# BpodFSM_r2_4.net
KiCad netlist of a schematic drawn in EAGLE
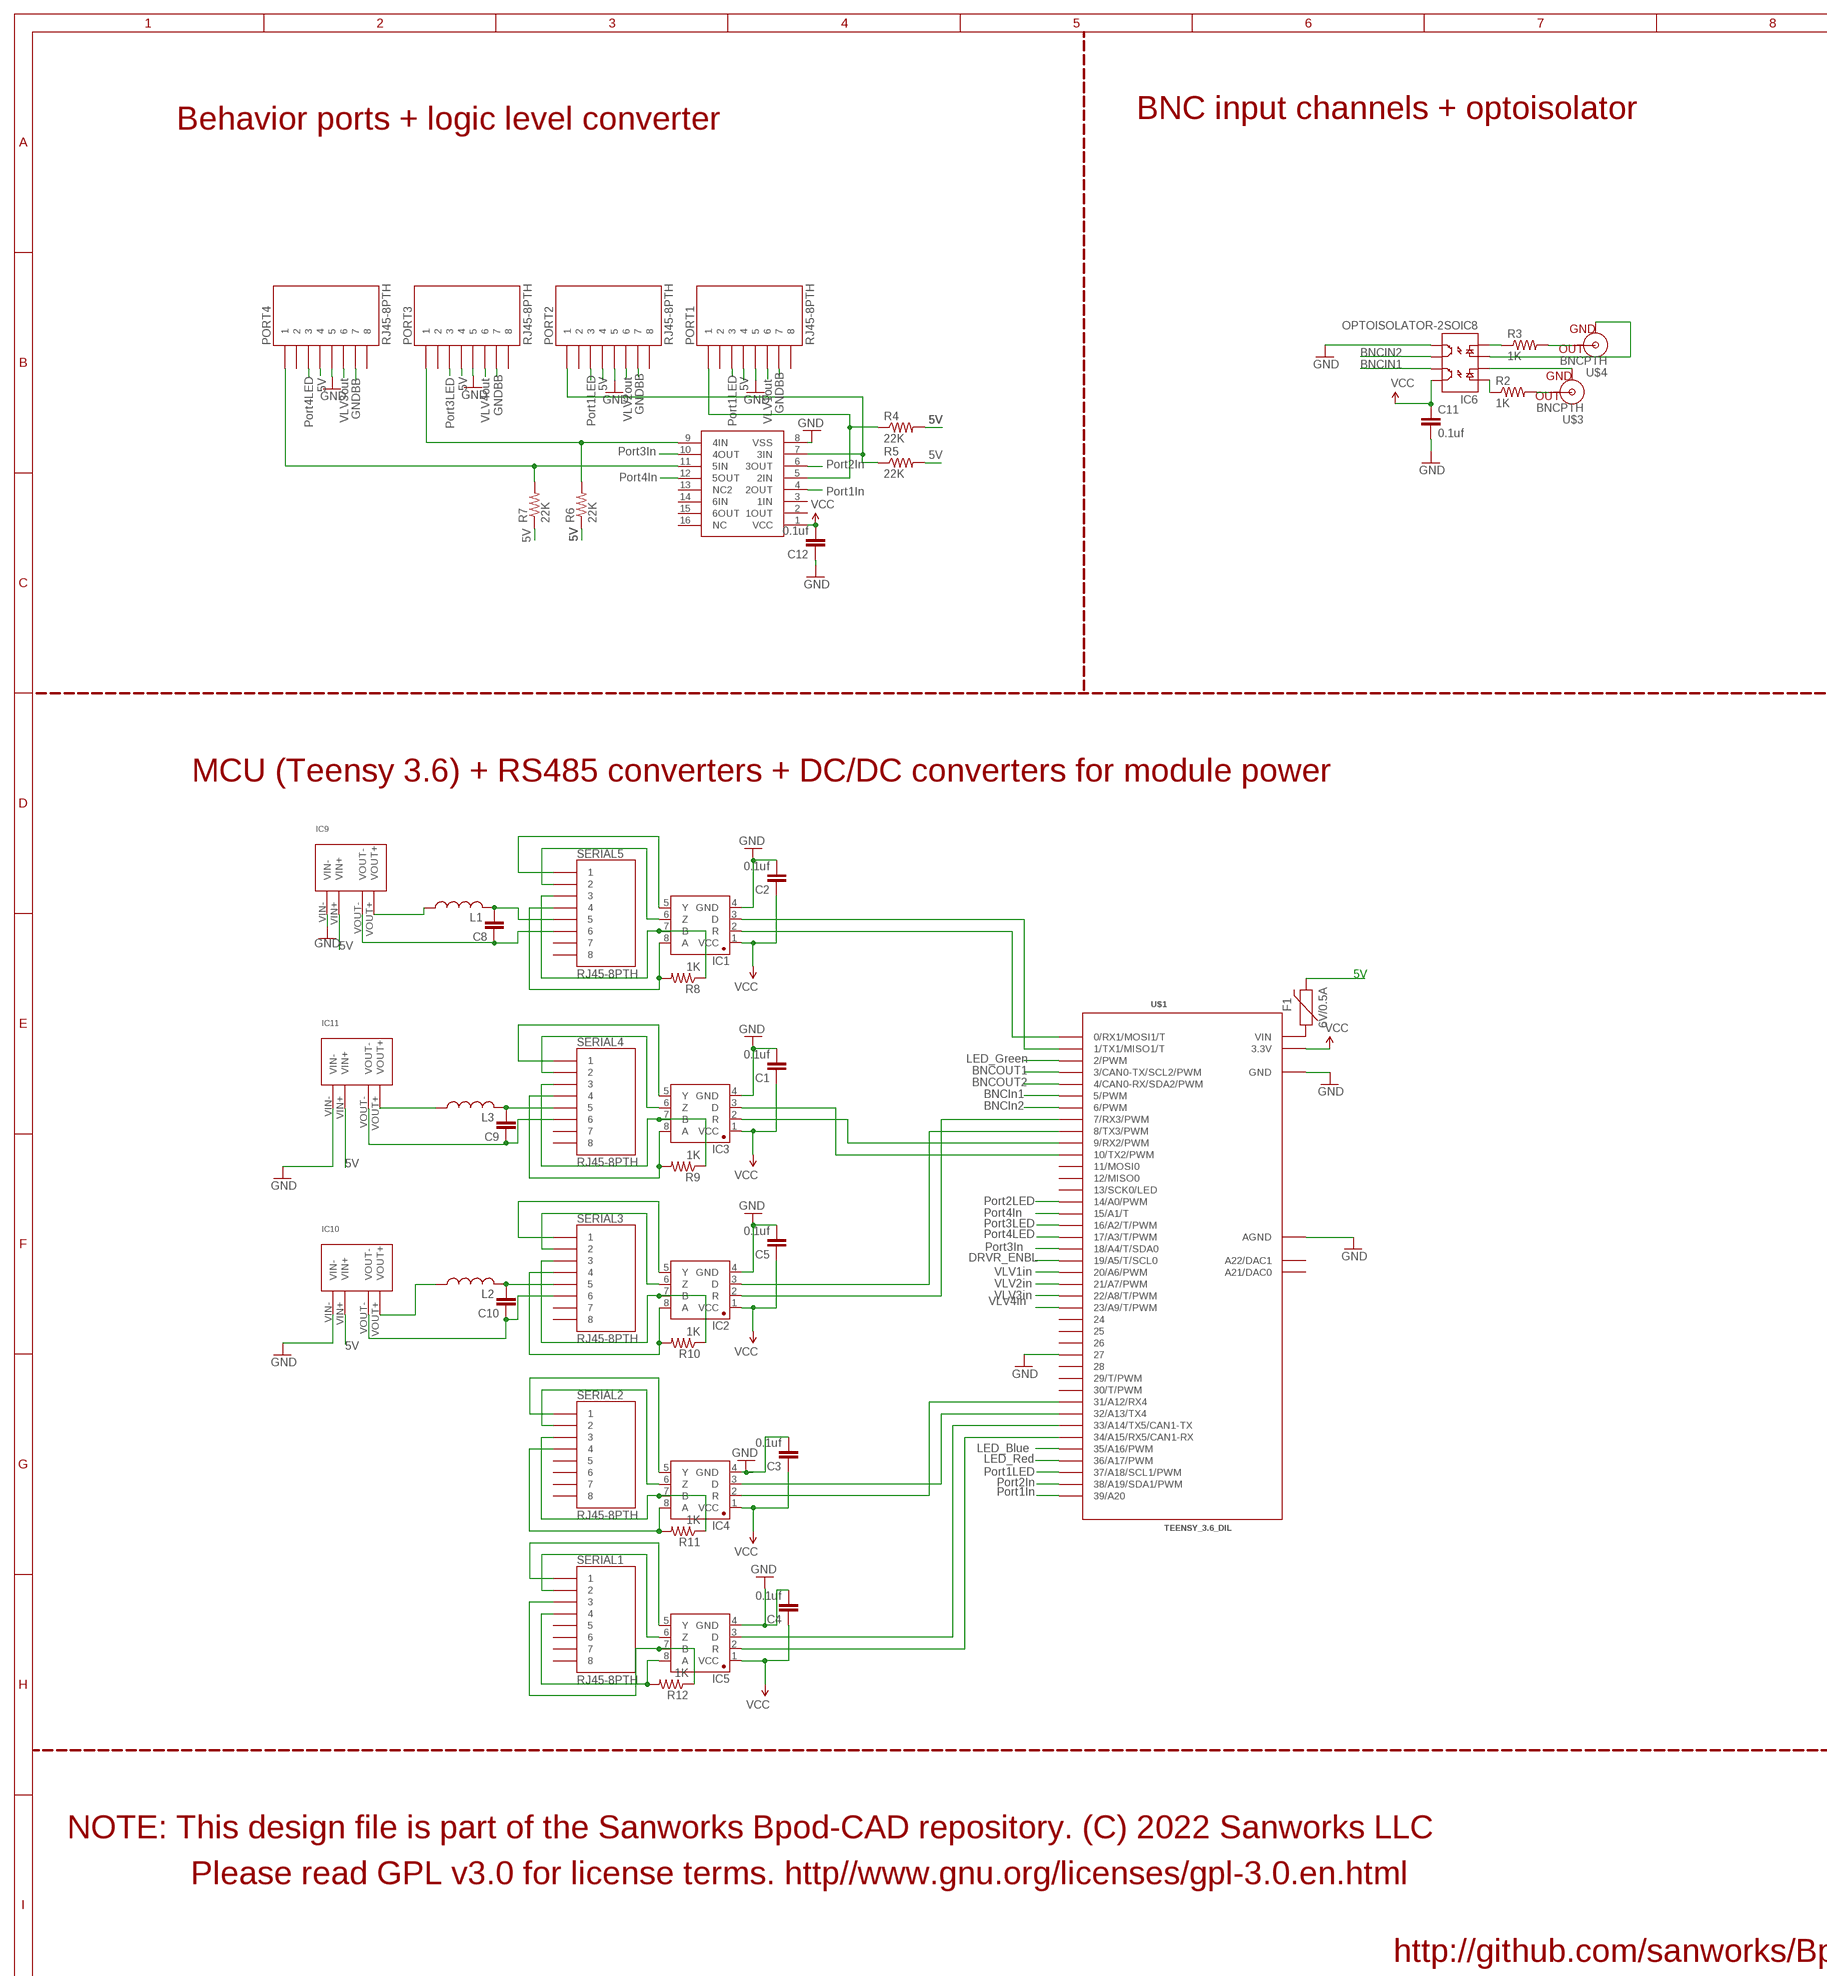
[diagram p0: schematic, sheet 1, part 1 of 2]
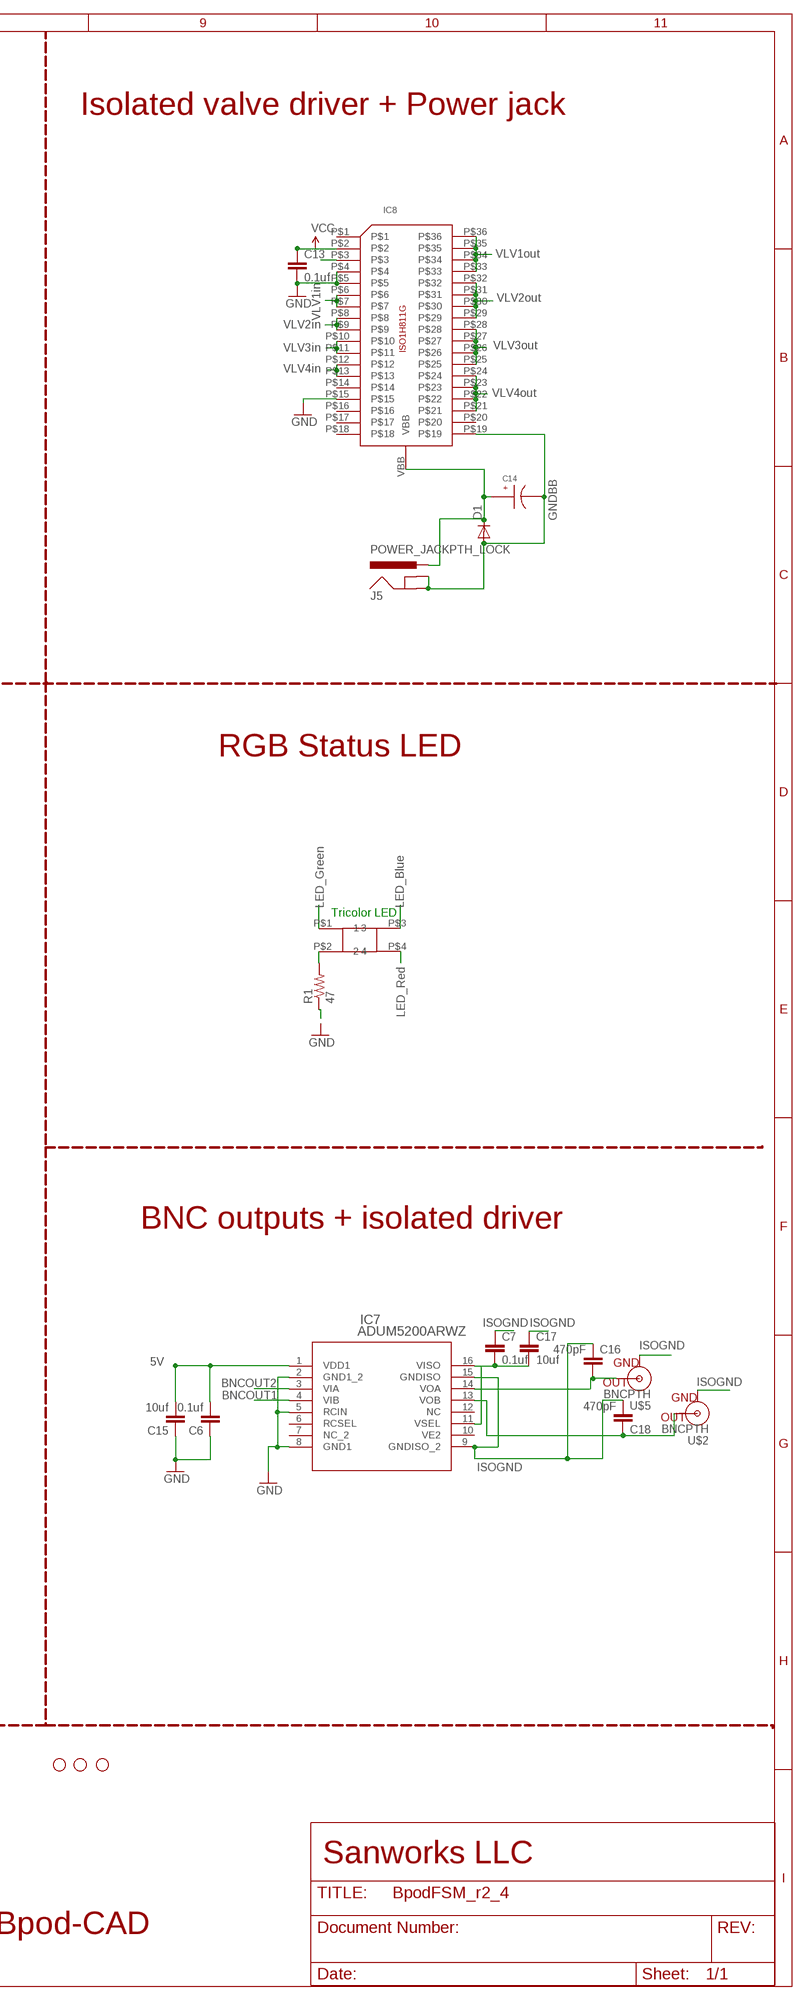
[diagram p1: schematic, sheet 1, part 2 of 2]

(export (version "E")
  (design (tool "Eeschema 10.0.6"))
  (components
    (comp (ref "C1")
      (value "0.1uf")
      (footprint "eagle-import:1206@1")
      (libsource (lib "eagle-import") (part "CAP1206"))
    )
    (comp (ref "C2")
      (value "0.1uf")
      (footprint "eagle-import:1206@1")
      (libsource (lib "eagle-import") (part "CAP1206"))
    )
    (comp (ref "C3")
      (value "0.1uf")
      (footprint "eagle-import:1206@1")
      (libsource (lib "eagle-import") (part "CAP1206"))
    )
    (comp (ref "C4")
      (value "0.1uf")
      (footprint "eagle-import:1206@1")
      (libsource (lib "eagle-import") (part "CAP1206"))
    )
    (comp (ref "C5")
      (value "0.1uf")
      (footprint "eagle-import:1206@1")
      (libsource (lib "eagle-import") (part "CAP1206"))
    )
    (comp (ref "C6")
      (value "0.1uf")
      (footprint "eagle-import:0805")
      (libsource (lib "eagle-import") (part "1.0UF-0805-25V-10%"))
    )
    (comp (ref "C7")
      (value "0.1uf")
      (footprint "eagle-import:0805")
      (libsource (lib "eagle-import") (part "1.0UF-0805-25V-10%"))
    )
    (comp (ref "C8")
      (value "CAP1206")
      (footprint "eagle-import:1206@1")
      (libsource (lib "eagle-import") (part "CAP1206"))
    )
    (comp (ref "C9")
      (value "CAP1206")
      (footprint "eagle-import:1206@1")
      (libsource (lib "eagle-import") (part "CAP1206"))
    )
    (comp (ref "C10")
      (value "CAP1206")
      (footprint "eagle-import:1206@1")
      (libsource (lib "eagle-import") (part "CAP1206"))
    )
    (comp (ref "C11")
      (value "0.1uf")
      (footprint "eagle-import:1206@1")
      (libsource (lib "eagle-import") (part "CAP1206"))
    )
    (comp (ref "C12")
      (value "0.1uf")
      (footprint "eagle-import:1206@1")
      (libsource (lib "eagle-import") (part "CAP1206"))
    )
    (comp (ref "C13")
      (value "0.1uf")
      (footprint "eagle-import:1206@1")
      (libsource (lib "eagle-import") (part "CAP1206"))
    )
    (comp (ref "C14")
      (value "EEE-FK1H100UR")
      (footprint "eagle-import:EEE-FK1H100UR")
      (libsource (lib "eagle-import") (part "EEE-FK1H100UR"))
    )
    (comp (ref "C15")
      (value "10uf")
      (footprint "eagle-import:1206@1")
      (libsource (lib "eagle-import") (part "CAP1206"))
    )
    (comp (ref "C16")
      (value "470pF")
      (footprint "eagle-import:0805")
      (libsource (lib "eagle-import") (part "1.0UF-0805-25V-10%"))
    )
    (comp (ref "C17")
      (value "10uf")
      (footprint "eagle-import:1206@1")
      (libsource (lib "eagle-import") (part "CAP1206"))
    )
    (comp (ref "C18")
      (value "470pF")
      (footprint "eagle-import:0805")
      (libsource (lib "eagle-import") (part "1.0UF-0805-25V-10%"))
    )
    (comp (ref "D1")
      (value "DIODE-DO214AA")
      (footprint "eagle-import:DO214AA")
      (libsource (lib "eagle-import") (part "DIODE-DO214AA"))
    )
    (comp (ref "F1")
      (value "6V/0.5A")
      (footprint "eagle-import:1206")
      (libsource (lib "eagle-import") (part "PPTC_HALF-AMP"))
    )
    (comp (ref "IC1")
      (value "SN65HVD31DR")
      (footprint "eagle-import:SO08")
      (libsource (lib "eagle-import") (part "SN65HVD31DR"))
    )
    (comp (ref "IC2")
      (value "SN65HVD31DR")
      (footprint "eagle-import:SO08")
      (libsource (lib "eagle-import") (part "SN65HVD31DR"))
    )
    (comp (ref "IC3")
      (value "SN65HVD31DR")
      (footprint "eagle-import:SO08")
      (libsource (lib "eagle-import") (part "SN65HVD31DR"))
    )
    (comp (ref "IC4")
      (value "SN65HVD31DR")
      (footprint "eagle-import:SO08")
      (libsource (lib "eagle-import") (part "SN65HVD31DR"))
    )
    (comp (ref "IC5")
      (value "SN65HVD31DR")
      (footprint "eagle-import:SO08")
      (libsource (lib "eagle-import") (part "SN65HVD31DR"))
    )
    (comp (ref "IC6")
      (value "OPTOISOLATOR-2SOIC8")
      (footprint "eagle-import:SO08-2")
      (libsource (lib "eagle-import") (part "OPTOISOLATOR-2SOIC8"))
    )
    (comp (ref "IC7")
      (value "ADUM5200ARWZ")
      (footprint "eagle-import:RW_16")
      (libsource (lib "eagle-import") (part "ADUM5200ARWZ"))
    )
    (comp (ref "IC8")
      (value "ISO1H811G")
      (footprint "eagle-import:ISO1H811G")
      (libsource (lib "eagle-import") (part "ISO1H811G"))
    )
    (comp (ref "IC9")
      (value "NME0509SC")
      (footprint "eagle-import:NME0509SC")
      (libsource (lib "eagle-import") (part "NME0509SC"))
    )
    (comp (ref "IC10")
      (value "NME0509SC")
      (footprint "eagle-import:NME0509SC")
      (libsource (lib "eagle-import") (part "NME0509SC"))
    )
    (comp (ref "IC11")
      (value "NME0509SC")
      (footprint "eagle-import:NME0509SC")
      (libsource (lib "eagle-import") (part "NME0509SC"))
    )
    (comp (ref "IC12")
      (value "CD4050")
      (footprint "eagle-import:SO16")
      (libsource (lib "eagle-import") (part "CD4050"))
    )
    (comp (ref "J5")
      (value "POWER_JACKPTH_LOCK")
      (footprint "eagle-import:POWER_JACK_PTH_LOCK")
      (libsource (lib "eagle-import") (part "POWER_JACKPTH_LOCK"))
    )
    (comp (ref "JP3")
      (value "STAND-OFF")
      (footprint "eagle-import:STAND-OFF")
      (libsource (lib "eagle-import") (part "STAND-OFF"))
    )
    (comp (ref "JP4")
      (value "STAND-OFF")
      (footprint "eagle-import:STAND-OFF")
      (libsource (lib "eagle-import") (part "STAND-OFF"))
    )
    (comp (ref "JP5")
      (value "STAND-OFF")
      (footprint "eagle-import:STAND-OFF")
      (libsource (lib "eagle-import") (part "STAND-OFF"))
    )
    (comp (ref "L1")
      (value "L-USL3225M")
      (footprint "eagle-import:L3225M")
      (libsource (lib "eagle-import") (part "L-USL3225M"))
    )
    (comp (ref "L2")
      (value "L-USL3225M")
      (footprint "eagle-import:L3225M")
      (libsource (lib "eagle-import") (part "L-USL3225M"))
    )
    (comp (ref "L3")
      (value "L-USL3225M")
      (footprint "eagle-import:L3225M")
      (libsource (lib "eagle-import") (part "L-USL3225M"))
    )
    (comp (ref "PORT1")
      (value "RJ45-8PTH")
      (footprint "eagle-import:RJ45-8")
      (libsource (lib "eagle-import") (part "RJ45-8PTH"))
    )
    (comp (ref "PORT2")
      (value "RJ45-8PTH")
      (footprint "eagle-import:RJ45-8")
      (libsource (lib "eagle-import") (part "RJ45-8PTH"))
    )
    (comp (ref "PORT3")
      (value "RJ45-8PTH")
      (footprint "eagle-import:RJ45-8")
      (libsource (lib "eagle-import") (part "RJ45-8PTH"))
    )
    (comp (ref "PORT4")
      (value "RJ45-8PTH")
      (footprint "eagle-import:RJ45-8")
      (libsource (lib "eagle-import") (part "RJ45-8PTH"))
    )
    (comp (ref "R1")
      (value "47")
      (footprint "eagle-import:1206")
      (libsource (lib "eagle-import") (part "RESISTOR1206"))
    )
    (comp (ref "R2")
      (value "1K")
      (footprint "eagle-import:1206")
      (libsource (lib "eagle-import") (part "SparkFun-Resistors_RESISTOR1206"))
    )
    (comp (ref "R3")
      (value "1K")
      (footprint "eagle-import:1206")
      (libsource (lib "eagle-import") (part "SparkFun-Resistors_RESISTOR1206"))
    )
    (comp (ref "R4")
      (value "22K")
      (footprint "eagle-import:1206")
      (libsource (lib "eagle-import") (part "SparkFun-Resistors_RESISTOR1206"))
    )
    (comp (ref "R5")
      (value "22K")
      (footprint "eagle-import:1206")
      (libsource (lib "eagle-import") (part "SparkFun-Resistors_RESISTOR1206"))
    )
    (comp (ref "R6")
      (value "22K")
      (footprint "eagle-import:1206")
      (libsource (lib "eagle-import") (part "SparkFun-Resistors_RESISTOR1206"))
    )
    (comp (ref "R7")
      (value "22K")
      (footprint "eagle-import:1206")
      (libsource (lib "eagle-import") (part "SparkFun-Resistors_RESISTOR1206"))
    )
    (comp (ref "R8")
      (value "1K")
      (footprint "eagle-import:1206")
      (libsource (lib "eagle-import") (part "SparkFun-Resistors_RESISTOR1206"))
    )
    (comp (ref "R9")
      (value "1K")
      (footprint "eagle-import:1206")
      (libsource (lib "eagle-import") (part "SparkFun-Resistors_RESISTOR1206"))
    )
    (comp (ref "R10")
      (value "1K")
      (footprint "eagle-import:1206")
      (libsource (lib "eagle-import") (part "SparkFun-Resistors_RESISTOR1206"))
    )
    (comp (ref "R11")
      (value "1K")
      (footprint "eagle-import:1206")
      (libsource (lib "eagle-import") (part "SparkFun-Resistors_RESISTOR1206"))
    )
    (comp (ref "R12")
      (value "1K")
      (footprint "eagle-import:1206")
      (libsource (lib "eagle-import") (part "SparkFun-Resistors_RESISTOR1206"))
    )
    (comp (ref "SERIAL1")
      (value "RJ45-8PTH")
      (footprint "eagle-import:RJ45-8")
      (libsource (lib "eagle-import") (part "RJ45-8PTH"))
    )
    (comp (ref "SERIAL2")
      (value "RJ45-8PTH")
      (footprint "eagle-import:RJ45-8")
      (libsource (lib "eagle-import") (part "RJ45-8PTH"))
    )
    (comp (ref "SERIAL3")
      (value "RJ45-8PTH")
      (footprint "eagle-import:RJ45-8")
      (libsource (lib "eagle-import") (part "RJ45-8PTH"))
    )
    (comp (ref "SERIAL4")
      (value "RJ45-8PTH")
      (footprint "eagle-import:RJ45-8")
      (libsource (lib "eagle-import") (part "RJ45-8PTH"))
    )
    (comp (ref "SERIAL5")
      (value "RJ45-8PTH")
      (footprint "eagle-import:RJ45-8")
      (libsource (lib "eagle-import") (part "RJ45-8PTH"))
    )
    (comp (ref "U$1")
      (value "TEENSY_3.6_DIL")
      (footprint "eagle-import:TEENSY_3.6_DIL")
      (libsource (lib "eagle-import") (part "TEENSY_3.6_DIL"))
    )
    (comp (ref "U$2")
      (value "BNCPTH")
      (footprint "eagle-import:BNC")
      (libsource (lib "eagle-import") (part "BNCPTH"))
    )
    (comp (ref "U$3")
      (value "BNCPTH")
      (footprint "eagle-import:BNC")
      (libsource (lib "eagle-import") (part "BNCPTH"))
    )
    (comp (ref "U$4")
      (value "BNCPTH")
      (footprint "eagle-import:BNC")
      (libsource (lib "eagle-import") (part "BNCPTH"))
    )
    (comp (ref "U$5")
      (value "BNCPTH")
      (footprint "eagle-import:BNC")
      (libsource (lib "eagle-import") (part "BNCPTH"))
    )
    (comp (ref "U$8")
      (value "SQUARE_TRICOLOR_LED")
      (footprint "eagle-import:SQUARE_TRICOLOR_LED")
      (libsource (lib "eagle-import") (part "SQUARE_TRICOLOR_LED"))
    )
  )
  (nets
    (net (code "1") (name "/5V") (class "Default")
      (node (ref "C15") (pin "2") (pinfunction "2_2") (pintype "passive"))
      (node (ref "C6") (pin "2") (pinfunction "2_2") (pintype "passive"))
      (node (ref "F1") (pin "2") (pinfunction "2_2") (pintype "bidirectional"))
      (node (ref "IC10") (pin "VIN+") (pinfunction "VIN+_VIN+") (pintype "bidirectional"))
      (node (ref "IC11") (pin "VIN+") (pinfunction "VIN+_VIN+") (pintype "bidirectional"))
      (node (ref "IC7") (pin "1") (pinfunction "VDD1_1") (pintype "passive"))
      (node (ref "IC9") (pin "VIN+") (pinfunction "VIN+_VIN+") (pintype "bidirectional"))
      (node (ref "PORT1") (pin "4") (pinfunction "4_4") (pintype "bidirectional"))
      (node (ref "PORT2") (pin "4") (pinfunction "4_4") (pintype "bidirectional"))
      (node (ref "PORT3") (pin "4") (pinfunction "4_4") (pintype "bidirectional"))
      (node (ref "PORT4") (pin "4") (pinfunction "4_4") (pintype "bidirectional"))
      (node (ref "R4") (pin "2") (pinfunction "2_2") (pintype "passive"))
      (node (ref "R5") (pin "2") (pinfunction "2_2") (pintype "passive"))
      (node (ref "R6") (pin "1") (pinfunction "1_1") (pintype "passive"))
      (node (ref "R7") (pin "1") (pinfunction "1_1") (pintype "passive"))
    )
    (net (code "2") (name "/BNCIN1") (class "Default")
      (node (ref "IC6") (pin "7") (pinfunction "EM1_7") (pintype "bidirectional"))
      (node (ref "U$1") (pin "6") (pinfunction "6/PWM_6") (pintype "bidirectional"))
    )
    (net (code "3") (name "/BNCIN2") (class "Default")
      (node (ref "IC6") (pin "6") (pinfunction "CL2_6") (pintype "bidirectional"))
      (node (ref "U$1") (pin "5") (pinfunction "5/PWM_5") (pintype "bidirectional"))
    )
    (net (code "4") (name "/BNCOUT1") (class "Default")
      (node (ref "IC7") (pin "4") (pinfunction "VIB_4") (pintype "passive"))
      (node (ref "U$1") (pin "4") (pinfunction "4/CAN0-RX/SDA2/PWM_4") (pintype "bidirectional"))
    )
    (net (code "5") (name "/BNCOUT2") (class "Default")
      (node (ref "IC7") (pin "3") (pinfunction "VIA_3") (pintype "passive"))
      (node (ref "U$1") (pin "3") (pinfunction "3/CAN0-TX/SCL2/PWM_3") (pintype "bidirectional"))
    )
    (net (code "6") (name "/DRVR_ENBL") (class "Default")
      (node (ref "IC8") (pin "P$3") (pinfunction "P$3_P$3") (pintype "bidirectional"))
      (node (ref "U$1") (pin "19/A5") (pinfunction "19/A5/T/SCL0_19/A5") (pintype "bidirectional"))
    )
    (net (code "7") (name "/GNDBB") (class "Default")
      (node (ref "C14") (pin "CATHODE") (pinfunction "CATHODE_CATHODE") (pintype "bidirectional"))
      (node (ref "D1") (pin "A") (pinfunction "A_A") (pintype "passive"))
      (node (ref "IC8") (pin "P$19") (pinfunction "P$19_P$19") (pintype "bidirectional"))
      (node (ref "J5") (pin "GND") (pinfunction "GND_GND") (pintype "bidirectional"))
      (node (ref "J5") (pin "GNDBREAK") (pinfunction "GNDBREAK_GNDBREAK") (pintype "bidirectional"))
      (node (ref "PORT1") (pin "7") (pinfunction "7_7") (pintype "bidirectional"))
      (node (ref "PORT2") (pin "7") (pinfunction "7_7") (pintype "bidirectional"))
      (node (ref "PORT3") (pin "7") (pinfunction "7_7") (pintype "bidirectional"))
      (node (ref "PORT4") (pin "7") (pinfunction "7_7") (pintype "bidirectional"))
    )
    (net (code "8") (name "/ISOGND") (class "Default")
      (node (ref "C16") (pin "2") (pinfunction "2_2") (pintype "passive"))
      (node (ref "C17") (pin "1") (pinfunction "1_1") (pintype "passive"))
      (node (ref "C18") (pin "2") (pinfunction "2_2") (pintype "passive"))
      (node (ref "C7") (pin "1") (pinfunction "1_1") (pintype "passive"))
      (node (ref "IC7") (pin "15") (pinfunction "GNDISO_15") (pintype "passive"))
      (node (ref "IC7") (pin "9") (pinfunction "GNDISO_2_9") (pintype "passive"))
      (node (ref "U$2") (pin "GND") (pinfunction "GND_GND") (pintype "bidirectional"))
      (node (ref "U$5") (pin "GND") (pinfunction "GND_GND") (pintype "bidirectional"))
    )
    (net (code "9") (name "/LED_BLUE") (class "Default")
      (node (ref "U$1") (pin "35/A16") (pinfunction "35/A16/PWM_35/A16") (pintype "bidirectional"))
      (node (ref "U$8") (pin "P$3") (pinfunction "3_P$3") (pintype "bidirectional"))
    )
    (net (code "10") (name "/LED_GREEN") (class "Default")
      (node (ref "U$1") (pin "2") (pinfunction "2/PWM_2") (pintype "bidirectional"))
      (node (ref "U$8") (pin "P$1") (pinfunction "1_P$1") (pintype "bidirectional"))
    )
    (net (code "11") (name "/LED_RED") (class "Default")
      (node (ref "U$1") (pin "36/A17") (pinfunction "36/A17/PWM_36/A17") (pintype "bidirectional"))
      (node (ref "U$8") (pin "P$4") (pinfunction "4_P$4") (pintype "bidirectional"))
    )
    (net (code "12") (name "/PORT1IN") (class "Default")
      (node (ref "IC12") (pin "4") (pinfunction "2OUT_4") (pintype "bidirectional"))
      (node (ref "U$1") (pin "39/A20") (pinfunction "39/A20_39/A20") (pintype "bidirectional"))
    )
    (net (code "13") (name "/PORT1LED") (class "Default")
      (node (ref "PORT1") (pin "3") (pinfunction "3_3") (pintype "bidirectional"))
      (node (ref "U$1") (pin "37/A18") (pinfunction "37/A18/SCL1/PWM_37/A18") (pintype "bidirectional"))
    )
    (net (code "14") (name "/PORT2IN") (class "Default")
      (node (ref "IC12") (pin "6") (pinfunction "3OUT_6") (pintype "bidirectional"))
      (node (ref "U$1") (pin "38/A19") (pinfunction "38/A19/SDA1/PWM_38/A19") (pintype "bidirectional"))
    )
    (net (code "15") (name "/PORT2LED") (class "Default")
      (node (ref "PORT2") (pin "3") (pinfunction "3_3") (pintype "bidirectional"))
      (node (ref "U$1") (pin "14/A0") (pinfunction "14/A0/PWM_14/A0") (pintype "bidirectional"))
    )
    (net (code "16") (name "/PORT3IN") (class "Default")
      (node (ref "IC12") (pin "10") (pinfunction "4OUT_10") (pintype "bidirectional"))
      (node (ref "U$1") (pin "18/A4") (pinfunction "18/A4/T/SDA0_18/A4") (pintype "bidirectional"))
    )
    (net (code "17") (name "/PORT3LED") (class "Default")
      (node (ref "PORT3") (pin "3") (pinfunction "3_3") (pintype "bidirectional"))
      (node (ref "U$1") (pin "16/A2") (pinfunction "16/A2/T/PWM_16/A2") (pintype "bidirectional"))
    )
    (net (code "18") (name "/PORT4IN") (class "Default")
      (node (ref "IC12") (pin "12") (pinfunction "5OUT_12") (pintype "bidirectional"))
      (node (ref "U$1") (pin "15/A1") (pinfunction "15/A1/T_15/A1") (pintype "bidirectional"))
    )
    (net (code "19") (name "/PORT4LED") (class "Default")
      (node (ref "PORT4") (pin "3") (pinfunction "3_3") (pintype "bidirectional"))
      (node (ref "U$1") (pin "17/A3") (pinfunction "17/A3/T/PWM_17/A3") (pintype "bidirectional"))
    )
    (net (code "20") (name "/VLV1IN") (class "Default")
      (node (ref "IC8") (pin "P$6") (pinfunction "P$6_P$6") (pintype "bidirectional"))
      (node (ref "IC8") (pin "P$7") (pinfunction "P$7_P$7") (pintype "bidirectional"))
      (node (ref "U$1") (pin "23/A9") (pinfunction "23/A9/T/PWM_23/A9") (pintype "bidirectional"))
    )
    (net (code "21") (name "/VLV1OUT") (class "Default")
      (node (ref "IC8") (pin "P$33") (pinfunction "P$33_P$33") (pintype "bidirectional"))
      (node (ref "IC8") (pin "P$34") (pinfunction "P$34_P$34") (pintype "bidirectional"))
      (node (ref "IC8") (pin "P$35") (pinfunction "P$35_P$35") (pintype "bidirectional"))
      (node (ref "IC8") (pin "P$36") (pinfunction "P$36_P$36") (pintype "bidirectional"))
      (node (ref "PORT1") (pin "6") (pinfunction "6_6") (pintype "bidirectional"))
    )
    (net (code "22") (name "/VLV2IN") (class "Default")
      (node (ref "IC8") (pin "P$8") (pinfunction "P$8_P$8") (pintype "bidirectional"))
      (node (ref "IC8") (pin "P$9") (pinfunction "P$9_P$9") (pintype "bidirectional"))
      (node (ref "U$1") (pin "22/A8") (pinfunction "22/A8/T/PWM_22/A8") (pintype "bidirectional"))
    )
    (net (code "23") (name "/VLV2OUT") (class "Default")
      (node (ref "IC8") (pin "P$29") (pinfunction "P$29_P$29") (pintype "bidirectional"))
      (node (ref "IC8") (pin "P$30") (pinfunction "P$30_P$30") (pintype "bidirectional"))
      (node (ref "IC8") (pin "P$31") (pinfunction "P$31_P$31") (pintype "bidirectional"))
      (node (ref "IC8") (pin "P$32") (pinfunction "P$32_P$32") (pintype "bidirectional"))
      (node (ref "PORT2") (pin "6") (pinfunction "6_6") (pintype "bidirectional"))
    )
    (net (code "24") (name "/VLV3IN") (class "Default")
      (node (ref "IC8") (pin "P$12") (pinfunction "P$12_P$12") (pintype "bidirectional"))
      (node (ref "IC8") (pin "P$13") (pinfunction "P$13_P$13") (pintype "bidirectional"))
      (node (ref "U$1") (pin "20/A6") (pinfunction "20/A6/PWM_20/A6") (pintype "bidirectional"))
    )
    (net (code "25") (name "/VLV3OUT") (class "Default")
      (node (ref "IC8") (pin "P$21") (pinfunction "P$21_P$21") (pintype "bidirectional"))
      (node (ref "IC8") (pin "P$22") (pinfunction "P$22_P$22") (pintype "bidirectional"))
      (node (ref "IC8") (pin "P$23") (pinfunction "P$23_P$23") (pintype "bidirectional"))
      (node (ref "IC8") (pin "P$24") (pinfunction "P$24_P$24") (pintype "bidirectional"))
      (node (ref "PORT3") (pin "6") (pinfunction "6_6") (pintype "bidirectional"))
    )
    (net (code "26") (name "/VLV4IN") (class "Default")
      (node (ref "IC8") (pin "P$10") (pinfunction "P$10_P$10") (pintype "bidirectional"))
      (node (ref "IC8") (pin "P$11") (pinfunction "P$11_P$11") (pintype "bidirectional"))
      (node (ref "U$1") (pin "21/A7") (pinfunction "21/A7/PWM_21/A7") (pintype "bidirectional"))
    )
    (net (code "27") (name "/VLV4OUT") (class "Default")
      (node (ref "IC8") (pin "P$25") (pinfunction "P$25_P$25") (pintype "bidirectional"))
      (node (ref "IC8") (pin "P$26") (pinfunction "P$26_P$26") (pintype "bidirectional"))
      (node (ref "IC8") (pin "P$27") (pinfunction "P$27_P$27") (pintype "bidirectional"))
      (node (ref "IC8") (pin "P$28") (pinfunction "P$28_P$28") (pintype "bidirectional"))
      (node (ref "PORT4") (pin "6") (pinfunction "6_6") (pintype "bidirectional"))
    )
    (net (code "28") (name "GND") (class "Default")
      (node (ref "C1") (pin "2") (pinfunction "2_2") (pintype "passive"))
      (node (ref "C11") (pin "2") (pinfunction "2_2") (pintype "passive"))
      (node (ref "C12") (pin "1") (pinfunction "1_1") (pintype "passive"))
      (node (ref "C13") (pin "2") (pinfunction "2_2") (pintype "passive"))
      (node (ref "C15") (pin "1") (pinfunction "1_1") (pintype "passive"))
      (node (ref "C2") (pin "2") (pinfunction "2_2") (pintype "passive"))
      (node (ref "C3") (pin "2") (pinfunction "2_2") (pintype "passive"))
      (node (ref "C4") (pin "2") (pinfunction "2_2") (pintype "passive"))
      (node (ref "C5") (pin "2") (pinfunction "2_2") (pintype "passive"))
      (node (ref "C6") (pin "1") (pinfunction "1_1") (pintype "passive"))
      (node (ref "IC1") (pin "4") (pinfunction "GND_4") (pintype "bidirectional"))
      (node (ref "IC10") (pin "VIN-") (pinfunction "VIN-_VIN-") (pintype "bidirectional"))
      (node (ref "IC11") (pin "VIN-") (pinfunction "VIN-_VIN-") (pintype "bidirectional"))
      (node (ref "IC12") (pin "8") (pinfunction "VSS_8") (pintype "bidirectional"))
      (node (ref "IC2") (pin "4") (pinfunction "GND_4") (pintype "bidirectional"))
      (node (ref "IC3") (pin "4") (pinfunction "GND_4") (pintype "bidirectional"))
      (node (ref "IC4") (pin "4") (pinfunction "GND_4") (pintype "bidirectional"))
      (node (ref "IC5") (pin "4") (pinfunction "GND_4") (pintype "bidirectional"))
      (node (ref "IC6") (pin "5") (pinfunction "EM2_5") (pintype "bidirectional"))
      (node (ref "IC7") (pin "2") (pinfunction "GND1_2_2") (pintype "passive"))
      (node (ref "IC7") (pin "5") (pinfunction "RCIN_5") (pintype "passive"))
      (node (ref "IC7") (pin "8") (pinfunction "GND1_8") (pintype "passive"))
      (node (ref "IC8") (pin "P$15") (pinfunction "P$15_P$15") (pintype "bidirectional"))
      (node (ref "IC8") (pin "P$4") (pinfunction "P$4_P$4") (pintype "bidirectional"))
      (node (ref "IC8") (pin "P$5") (pinfunction "P$5_P$5") (pintype "bidirectional"))
      (node (ref "IC9") (pin "VIN-") (pinfunction "VIN-_VIN-") (pintype "bidirectional"))
      (node (ref "PORT1") (pin "5") (pinfunction "5_5") (pintype "bidirectional"))
      (node (ref "PORT2") (pin "5") (pinfunction "5_5") (pintype "bidirectional"))
      (node (ref "PORT3") (pin "5") (pinfunction "5_5") (pintype "bidirectional"))
      (node (ref "PORT4") (pin "5") (pinfunction "5_5") (pintype "bidirectional"))
      (node (ref "R1") (pin "1") (pinfunction "1_1") (pintype "passive"))
      (node (ref "U$1") (pin "27") (pinfunction "27_27") (pintype "bidirectional"))
      (node (ref "U$1") (pin "AGND") (pinfunction "AGND_AGND") (pintype "power_in"))
      (node (ref "U$1") (pin "GND") (pinfunction "GND_GND") (pintype "power_in"))
      (node (ref "U$1") (pin "GND1") (pinfunction "GND_GND1") (pintype "power_in"))
    )
    (net (code "29") (name "Net-(C8-Pad1)") (class "Default")
      (node (ref "C8") (pin "1") (pinfunction "1_1") (pintype "passive"))
      (node (ref "IC9") (pin "VOUT-") (pinfunction "VOUT-_VOUT-") (pintype "bidirectional"))
      (node (ref "SERIAL5") (pin "6") (pinfunction "6_6") (pintype "bidirectional"))
    )
    (net (code "30") (name "Net-(C8-Pad2)") (class "Default")
      (node (ref "C8") (pin "2") (pinfunction "2_2") (pintype "passive"))
      (node (ref "L1") (pin "2") (pinfunction "2_2") (pintype "passive"))
      (node (ref "SERIAL5") (pin "5") (pinfunction "5_5") (pintype "bidirectional"))
    )
    (net (code "31") (name "Net-(C9-Pad1)") (class "Default")
      (node (ref "C9") (pin "1") (pinfunction "1_1") (pintype "passive"))
      (node (ref "IC11") (pin "VOUT-") (pinfunction "VOUT-_VOUT-") (pintype "bidirectional"))
      (node (ref "SERIAL4") (pin "6") (pinfunction "6_6") (pintype "bidirectional"))
    )
    (net (code "32") (name "Net-(C9-Pad2)") (class "Default")
      (node (ref "C9") (pin "2") (pinfunction "2_2") (pintype "passive"))
      (node (ref "L3") (pin "2") (pinfunction "2_2") (pintype "passive"))
      (node (ref "SERIAL4") (pin "5") (pinfunction "5_5") (pintype "bidirectional"))
    )
    (net (code "33") (name "Net-(C10-Pad1)") (class "Default")
      (node (ref "C10") (pin "1") (pinfunction "1_1") (pintype "passive"))
      (node (ref "IC10") (pin "VOUT-") (pinfunction "VOUT-_VOUT-") (pintype "bidirectional"))
      (node (ref "SERIAL3") (pin "6") (pinfunction "6_6") (pintype "bidirectional"))
    )
    (net (code "34") (name "Net-(C10-Pad2)") (class "Default")
      (node (ref "C10") (pin "2") (pinfunction "2_2") (pintype "passive"))
      (node (ref "L2") (pin "2") (pinfunction "2_2") (pintype "passive"))
      (node (ref "SERIAL3") (pin "5") (pinfunction "5_5") (pintype "bidirectional"))
    )
    (net (code "35") (name "Net-(C14-PadANODE)") (class "Default")
      (node (ref "C14") (pin "ANODE") (pinfunction "ANODE_ANODE") (pintype "bidirectional"))
      (node (ref "D1") (pin "C") (pinfunction "C_C") (pintype "passive"))
      (node (ref "IC8") (pin "VBB") (pinfunction "VBB_VBB") (pintype "bidirectional"))
      (node (ref "J5") (pin "PWR") (pinfunction "PWR_PWR") (pintype "bidirectional"))
    )
    (net (code "36") (name "Net-(F1-Pad1)") (class "Default")
      (node (ref "F1") (pin "1") (pinfunction "1_1") (pintype "bidirectional"))
      (node (ref "U$1") (pin "VIN") (pinfunction "VIN_VIN") (pintype "power_in"))
    )
    (net (code "37") (name "Net-(IC1-A)") (class "Default")
      (node (ref "IC1") (pin "8") (pinfunction "A_8") (pintype "bidirectional"))
      (node (ref "R8") (pin "2") (pinfunction "2_2") (pintype "passive"))
      (node (ref "SERIAL5") (pin "4") (pinfunction "4_4") (pintype "bidirectional"))
    )
    (net (code "38") (name "Net-(IC1-B)") (class "Default")
      (node (ref "IC1") (pin "7") (pinfunction "B_7") (pintype "bidirectional"))
      (node (ref "R8") (pin "1") (pinfunction "1_1") (pintype "passive"))
      (node (ref "SERIAL5") (pin "3") (pinfunction "3_3") (pintype "bidirectional"))
    )
    (net (code "39") (name "Net-(IC1-D)") (class "Default")
      (node (ref "IC1") (pin "3") (pinfunction "D_3") (pintype "bidirectional"))
      (node (ref "U$1") (pin "1") (pinfunction "1/TX1/MISO1/T_1") (pintype "bidirectional"))
    )
    (net (code "40") (name "Net-(IC1-R)") (class "Default")
      (node (ref "IC1") (pin "2") (pinfunction "R_2") (pintype "bidirectional"))
      (node (ref "U$1") (pin "0") (pinfunction "0/RX1/MOSI1/T_0") (pintype "bidirectional"))
    )
    (net (code "41") (name "Net-(IC1-Y)") (class "Default")
      (node (ref "IC1") (pin "5") (pinfunction "Y_5") (pintype "bidirectional"))
      (node (ref "SERIAL5") (pin "1") (pinfunction "1_1") (pintype "bidirectional"))
    )
    (net (code "42") (name "Net-(IC1-Z)") (class "Default")
      (node (ref "IC1") (pin "6") (pinfunction "Z_6") (pintype "bidirectional"))
      (node (ref "SERIAL5") (pin "2") (pinfunction "2_2") (pintype "bidirectional"))
    )
    (net (code "43") (name "Net-(IC2-A)") (class "Default")
      (node (ref "IC2") (pin "8") (pinfunction "A_8") (pintype "bidirectional"))
      (node (ref "R10") (pin "2") (pinfunction "2_2") (pintype "passive"))
      (node (ref "SERIAL3") (pin "4") (pinfunction "4_4") (pintype "bidirectional"))
    )
    (net (code "44") (name "Net-(IC2-B)") (class "Default")
      (node (ref "IC2") (pin "7") (pinfunction "B_7") (pintype "bidirectional"))
      (node (ref "R10") (pin "1") (pinfunction "1_1") (pintype "passive"))
      (node (ref "SERIAL3") (pin "3") (pinfunction "3_3") (pintype "bidirectional"))
    )
    (net (code "45") (name "Net-(IC2-D)") (class "Default")
      (node (ref "IC2") (pin "3") (pinfunction "D_3") (pintype "bidirectional"))
      (node (ref "U$1") (pin "8") (pinfunction "8/TX3/PWM_8") (pintype "bidirectional"))
    )
    (net (code "46") (name "Net-(IC2-R)") (class "Default")
      (node (ref "IC2") (pin "2") (pinfunction "R_2") (pintype "bidirectional"))
      (node (ref "U$1") (pin "7") (pinfunction "7/RX3/PWM_7") (pintype "bidirectional"))
    )
    (net (code "47") (name "Net-(IC2-Y)") (class "Default")
      (node (ref "IC2") (pin "5") (pinfunction "Y_5") (pintype "bidirectional"))
      (node (ref "SERIAL3") (pin "1") (pinfunction "1_1") (pintype "bidirectional"))
    )
    (net (code "48") (name "Net-(IC2-Z)") (class "Default")
      (node (ref "IC2") (pin "6") (pinfunction "Z_6") (pintype "bidirectional"))
      (node (ref "SERIAL3") (pin "2") (pinfunction "2_2") (pintype "bidirectional"))
    )
    (net (code "49") (name "Net-(IC3-A)") (class "Default")
      (node (ref "IC3") (pin "8") (pinfunction "A_8") (pintype "bidirectional"))
      (node (ref "R9") (pin "2") (pinfunction "2_2") (pintype "passive"))
      (node (ref "SERIAL4") (pin "4") (pinfunction "4_4") (pintype "bidirectional"))
    )
    (net (code "50") (name "Net-(IC3-B)") (class "Default")
      (node (ref "IC3") (pin "7") (pinfunction "B_7") (pintype "bidirectional"))
      (node (ref "R9") (pin "1") (pinfunction "1_1") (pintype "passive"))
      (node (ref "SERIAL4") (pin "3") (pinfunction "3_3") (pintype "bidirectional"))
    )
    (net (code "51") (name "Net-(IC3-D)") (class "Default")
      (node (ref "IC3") (pin "3") (pinfunction "D_3") (pintype "bidirectional"))
      (node (ref "U$1") (pin "10") (pinfunction "10/TX2/PWM_10") (pintype "bidirectional"))
    )
    (net (code "52") (name "Net-(IC3-R)") (class "Default")
      (node (ref "IC3") (pin "2") (pinfunction "R_2") (pintype "bidirectional"))
      (node (ref "U$1") (pin "9") (pinfunction "9/RX2/PWM_9") (pintype "bidirectional"))
    )
    (net (code "53") (name "Net-(IC3-Y)") (class "Default")
      (node (ref "IC3") (pin "5") (pinfunction "Y_5") (pintype "bidirectional"))
      (node (ref "SERIAL4") (pin "1") (pinfunction "1_1") (pintype "bidirectional"))
    )
    (net (code "54") (name "Net-(IC3-Z)") (class "Default")
      (node (ref "IC3") (pin "6") (pinfunction "Z_6") (pintype "bidirectional"))
      (node (ref "SERIAL4") (pin "2") (pinfunction "2_2") (pintype "bidirectional"))
    )
    (net (code "55") (name "Net-(IC4-A)") (class "Default")
      (node (ref "IC4") (pin "8") (pinfunction "A_8") (pintype "bidirectional"))
      (node (ref "R11") (pin "2") (pinfunction "2_2") (pintype "passive"))
      (node (ref "SERIAL2") (pin "4") (pinfunction "4_4") (pintype "bidirectional"))
    )
    (net (code "56") (name "Net-(IC4-B)") (class "Default")
      (node (ref "IC4") (pin "7") (pinfunction "B_7") (pintype "bidirectional"))
      (node (ref "R11") (pin "1") (pinfunction "1_1") (pintype "passive"))
      (node (ref "SERIAL2") (pin "3") (pinfunction "3_3") (pintype "bidirectional"))
    )
    (net (code "57") (name "Net-(IC4-D)") (class "Default")
      (node (ref "IC4") (pin "3") (pinfunction "D_3") (pintype "bidirectional"))
      (node (ref "U$1") (pin "32/A13") (pinfunction "32/A13/TX4_32/A13") (pintype "bidirectional"))
    )
    (net (code "58") (name "Net-(IC4-R)") (class "Default")
      (node (ref "IC4") (pin "2") (pinfunction "R_2") (pintype "bidirectional"))
      (node (ref "U$1") (pin "31/A12") (pinfunction "31/A12/RX4_31/A12") (pintype "bidirectional"))
    )
    (net (code "59") (name "Net-(IC4-Y)") (class "Default")
      (node (ref "IC4") (pin "5") (pinfunction "Y_5") (pintype "bidirectional"))
      (node (ref "SERIAL2") (pin "1") (pinfunction "1_1") (pintype "bidirectional"))
    )
    (net (code "60") (name "Net-(IC4-Z)") (class "Default")
      (node (ref "IC4") (pin "6") (pinfunction "Z_6") (pintype "bidirectional"))
      (node (ref "SERIAL2") (pin "2") (pinfunction "2_2") (pintype "bidirectional"))
    )
    (net (code "61") (name "Net-(IC5-A)") (class "Default")
      (node (ref "IC5") (pin "8") (pinfunction "A_8") (pintype "bidirectional"))
      (node (ref "R12") (pin "2") (pinfunction "2_2") (pintype "passive"))
      (node (ref "SERIAL1") (pin "4") (pinfunction "4_4") (pintype "bidirectional"))
    )
    (net (code "62") (name "Net-(IC5-B)") (class "Default")
      (node (ref "IC5") (pin "7") (pinfunction "B_7") (pintype "bidirectional"))
      (node (ref "R12") (pin "1") (pinfunction "1_1") (pintype "passive"))
      (node (ref "SERIAL1") (pin "3") (pinfunction "3_3") (pintype "bidirectional"))
    )
    (net (code "63") (name "Net-(IC5-D)") (class "Default")
      (node (ref "IC5") (pin "3") (pinfunction "D_3") (pintype "bidirectional"))
      (node (ref "U$1") (pin "33/A14") (pinfunction "33/A14/TX5/CAN1-TX_33/A14") (pintype "bidirectional"))
    )
    (net (code "64") (name "Net-(IC5-R)") (class "Default")
      (node (ref "IC5") (pin "2") (pinfunction "R_2") (pintype "bidirectional"))
      (node (ref "U$1") (pin "34/A15") (pinfunction "34/A15/RX5/CAN1-RX_34/A15") (pintype "bidirectional"))
    )
    (net (code "65") (name "Net-(IC5-Y)") (class "Default")
      (node (ref "IC5") (pin "5") (pinfunction "Y_5") (pintype "bidirectional"))
      (node (ref "SERIAL1") (pin "1") (pinfunction "1_1") (pintype "bidirectional"))
    )
    (net (code "66") (name "Net-(IC5-Z)") (class "Default")
      (node (ref "IC5") (pin "6") (pinfunction "Z_6") (pintype "bidirectional"))
      (node (ref "SERIAL1") (pin "2") (pinfunction "2_2") (pintype "bidirectional"))
    )
    (net (code "67") (name "Net-(IC6-A1)") (class "Default")
      (node (ref "IC6") (pin "1") (pinfunction "A1_1") (pintype "bidirectional"))
      (node (ref "R2") (pin "1") (pinfunction "1_1") (pintype "passive"))
    )
    (net (code "68") (name "Net-(IC6-A2)") (class "Default")
      (node (ref "IC6") (pin "3") (pinfunction "A2_3") (pintype "bidirectional"))
      (node (ref "U$4") (pin "GND") (pinfunction "GND_GND") (pintype "bidirectional"))
    )
    (net (code "69") (name "Net-(IC6-C1)") (class "Default")
      (node (ref "IC6") (pin "2") (pinfunction "C1_2") (pintype "bidirectional"))
      (node (ref "U$3") (pin "GND") (pinfunction "GND_GND") (pintype "bidirectional"))
    )
    (net (code "70") (name "Net-(IC6-C2)") (class "Default")
      (node (ref "IC6") (pin "4") (pinfunction "C2_4") (pintype "bidirectional"))
      (node (ref "R3") (pin "1") (pinfunction "1_1") (pintype "passive"))
    )
    (net (code "71") (name "Net-(IC7-VISO)") (class "Default")
      (node (ref "C17") (pin "2") (pinfunction "2_2") (pintype "passive"))
      (node (ref "C7") (pin "2") (pinfunction "2_2") (pintype "passive"))
      (node (ref "IC7") (pin "11") (pinfunction "VSEL_11") (pintype "passive"))
      (node (ref "IC7") (pin "16") (pinfunction "VISO_16") (pintype "passive"))
    )
    (net (code "72") (name "Net-(IC7-VOA)") (class "Default")
      (node (ref "C16") (pin "1") (pinfunction "1_1") (pintype "passive"))
      (node (ref "IC7") (pin "14") (pinfunction "VOA_14") (pintype "passive"))
      (node (ref "U$5") (pin "S") (pinfunction "OUT_S") (pintype "bidirectional"))
    )
    (net (code "73") (name "Net-(IC7-VOB)") (class "Default")
      (node (ref "C18") (pin "1") (pinfunction "1_1") (pintype "passive"))
      (node (ref "IC7") (pin "13") (pinfunction "VOB_13") (pintype "passive"))
      (node (ref "U$2") (pin "S") (pinfunction "OUT_S") (pintype "bidirectional"))
    )
    (net (code "74") (name "Net-(IC9-PadVOUT+)") (class "Default")
      (node (ref "IC9") (pin "VOUT+") (pinfunction "VOUT+_VOUT+") (pintype "bidirectional"))
      (node (ref "L1") (pin "1") (pinfunction "1_1") (pintype "passive"))
    )
    (net (code "75") (name "Net-(IC10-PadVOUT+)") (class "Default")
      (node (ref "IC10") (pin "VOUT+") (pinfunction "VOUT+_VOUT+") (pintype "bidirectional"))
      (node (ref "L2") (pin "1") (pinfunction "1_1") (pintype "passive"))
    )
    (net (code "76") (name "Net-(IC11-PadVOUT+)") (class "Default")
      (node (ref "IC11") (pin "VOUT+") (pinfunction "VOUT+_VOUT+") (pintype "bidirectional"))
      (node (ref "L3") (pin "1") (pinfunction "1_1") (pintype "passive"))
    )
    (net (code "77") (name "Net-(IC12-2IN)") (class "Default")
      (node (ref "IC12") (pin "5") (pinfunction "2IN_5") (pintype "bidirectional"))
      (node (ref "PORT1") (pin "1") (pinfunction "1_1") (pintype "bidirectional"))
      (node (ref "R4") (pin "1") (pinfunction "1_1") (pintype "passive"))
    )
    (net (code "78") (name "Net-(IC12-3IN)") (class "Default")
      (node (ref "IC12") (pin "7") (pinfunction "3IN_7") (pintype "bidirectional"))
      (node (ref "PORT2") (pin "1") (pinfunction "1_1") (pintype "bidirectional"))
      (node (ref "R5") (pin "1") (pinfunction "1_1") (pintype "passive"))
    )
    (net (code "79") (name "Net-(IC12-4IN)") (class "Default")
      (node (ref "IC12") (pin "9") (pinfunction "4IN_9") (pintype "bidirectional"))
      (node (ref "PORT3") (pin "1") (pinfunction "1_1") (pintype "bidirectional"))
      (node (ref "R6") (pin "2") (pinfunction "2_2") (pintype "passive"))
    )
    (net (code "80") (name "Net-(IC12-5IN)") (class "Default")
      (node (ref "IC12") (pin "11") (pinfunction "5IN_11") (pintype "bidirectional"))
      (node (ref "PORT4") (pin "1") (pinfunction "1_1") (pintype "bidirectional"))
      (node (ref "R7") (pin "2") (pinfunction "2_2") (pintype "passive"))
    )
    (net (code "81") (name "Net-(U$3-OUT)") (class "Default")
      (node (ref "R2") (pin "2") (pinfunction "2_2") (pintype "passive"))
      (node (ref "U$3") (pin "S") (pinfunction "OUT_S") (pintype "bidirectional"))
    )
    (net (code "82") (name "Net-(U$4-OUT)") (class "Default")
      (node (ref "R3") (pin "2") (pinfunction "2_2") (pintype "passive"))
      (node (ref "U$4") (pin "S") (pinfunction "OUT_S") (pintype "bidirectional"))
    )
    (net (code "83") (name "Net-(U$8-2)") (class "Default")
      (node (ref "R1") (pin "2") (pinfunction "2_2") (pintype "passive"))
      (node (ref "U$8") (pin "P$2") (pinfunction "2_P$2") (pintype "bidirectional"))
    )
    (net (code "84") (name "VCC") (class "Default")
      (node (ref "C1") (pin "1") (pinfunction "1_1") (pintype "passive"))
      (node (ref "C11") (pin "1") (pinfunction "1_1") (pintype "passive"))
      (node (ref "C12") (pin "2") (pinfunction "2_2") (pintype "passive"))
      (node (ref "C13") (pin "1") (pinfunction "1_1") (pintype "passive"))
      (node (ref "C2") (pin "1") (pinfunction "1_1") (pintype "passive"))
      (node (ref "C3") (pin "1") (pinfunction "1_1") (pintype "passive"))
      (node (ref "C4") (pin "1") (pinfunction "1_1") (pintype "passive"))
      (node (ref "C5") (pin "1") (pinfunction "1_1") (pintype "passive"))
      (node (ref "IC1") (pin "1") (pinfunction "VCC_1") (pintype "bidirectional"))
      (node (ref "IC12") (pin "1") (pinfunction "VCC_1") (pintype "bidirectional"))
      (node (ref "IC2") (pin "1") (pinfunction "VCC_1") (pintype "bidirectional"))
      (node (ref "IC3") (pin "1") (pinfunction "VCC_1") (pintype "bidirectional"))
      (node (ref "IC4") (pin "1") (pinfunction "VCC_1") (pintype "bidirectional"))
      (node (ref "IC5") (pin "1") (pinfunction "VCC_1") (pintype "bidirectional"))
      (node (ref "IC6") (pin "8") (pinfunction "CL1_8") (pintype "bidirectional"))
      (node (ref "IC8") (pin "P$2") (pinfunction "P$2_P$2") (pintype "bidirectional"))
      (node (ref "U$1") (pin "3.3V") (pinfunction "3.3V_3.3V") (pintype "power_in"))
      (node (ref "U$1") (pin "3.3V3") (pinfunction "3.3V_3.3V3") (pintype "power_in"))
    )
    (net (code "85") (name "unconnected-(IC7-NC-Pad12)") (class "Default")
      (node (ref "IC7") (pin "12") (pinfunction "NC_12") (pintype "passive"))
    )
    (net (code "86") (name "unconnected-(IC7-NC_2-Pad7)") (class "Default")
      (node (ref "IC7") (pin "7") (pinfunction "NC_2_7") (pintype "passive"))
    )
    (net (code "87") (name "unconnected-(IC7-RCSEL-Pad6)") (class "Default")
      (node (ref "IC7") (pin "6") (pinfunction "RCSEL_6") (pintype "passive"))
    )
    (net (code "88") (name "unconnected-(IC7-VE2-Pad10)") (class "Default")
      (node (ref "IC7") (pin "10") (pinfunction "VE2_10") (pintype "passive"))
    )
    (net (code "89") (name "unconnected-(IC8-PadP$1)") (class "Default")
      (node (ref "IC8") (pin "P$1") (pinfunction "P$1_P$1") (pintype "bidirectional"))
    )
    (net (code "90") (name "unconnected-(IC8-PadP$14)") (class "Default")
      (node (ref "IC8") (pin "P$14") (pinfunction "P$14_P$14") (pintype "bidirectional"))
    )
    (net (code "91") (name "unconnected-(IC8-PadP$16)") (class "Default")
      (node (ref "IC8") (pin "P$16") (pinfunction "P$16_P$16") (pintype "bidirectional"))
    )
    (net (code "92") (name "unconnected-(IC8-PadP$17)") (class "Default")
      (node (ref "IC8") (pin "P$17") (pinfunction "P$17_P$17") (pintype "bidirectional"))
    )
    (net (code "93") (name "unconnected-(IC8-PadP$18)") (class "Default")
      (node (ref "IC8") (pin "P$18") (pinfunction "P$18_P$18") (pintype "bidirectional"))
    )
    (net (code "94") (name "unconnected-(IC8-PadP$20)") (class "Default")
      (node (ref "IC8") (pin "P$20") (pinfunction "P$20_P$20") (pintype "bidirectional"))
    )
    (net (code "95") (name "unconnected-(IC12-1IN-Pad3)") (class "Default")
      (node (ref "IC12") (pin "3") (pinfunction "1IN_3") (pintype "bidirectional"))
    )
    (net (code "96") (name "unconnected-(IC12-1OUT-Pad2)") (class "Default")
      (node (ref "IC12") (pin "2") (pinfunction "1OUT_2") (pintype "bidirectional"))
    )
    (net (code "97") (name "unconnected-(IC12-6IN-Pad14)") (class "Default")
      (node (ref "IC12") (pin "14") (pinfunction "6IN_14") (pintype "bidirectional"))
    )
    (net (code "98") (name "unconnected-(IC12-6OUT-Pad15)") (class "Default")
      (node (ref "IC12") (pin "15") (pinfunction "6OUT_15") (pintype "bidirectional"))
    )
    (net (code "99") (name "unconnected-(IC12-NC-Pad16)") (class "Default")
      (node (ref "IC12") (pin "16") (pinfunction "NC_16") (pintype "bidirectional"))
    )
    (net (code "100") (name "unconnected-(IC12-NC2-Pad13)") (class "Default")
      (node (ref "IC12") (pin "13") (pinfunction "NC2_13") (pintype "bidirectional"))
    )
    (net (code "101") (name "unconnected-(PORT1-Pad2)") (class "Default")
      (node (ref "PORT1") (pin "2") (pinfunction "2_2") (pintype "bidirectional"))
    )
    (net (code "102") (name "unconnected-(PORT1-Pad8)") (class "Default")
      (node (ref "PORT1") (pin "8") (pinfunction "8_8") (pintype "bidirectional"))
    )
    (net (code "103") (name "unconnected-(PORT2-Pad2)") (class "Default")
      (node (ref "PORT2") (pin "2") (pinfunction "2_2") (pintype "bidirectional"))
    )
    (net (code "104") (name "unconnected-(PORT2-Pad8)") (class "Default")
      (node (ref "PORT2") (pin "8") (pinfunction "8_8") (pintype "bidirectional"))
    )
    (net (code "105") (name "unconnected-(PORT3-Pad2)") (class "Default")
      (node (ref "PORT3") (pin "2") (pinfunction "2_2") (pintype "bidirectional"))
    )
    (net (code "106") (name "unconnected-(PORT3-Pad8)") (class "Default")
      (node (ref "PORT3") (pin "8") (pinfunction "8_8") (pintype "bidirectional"))
    )
    (net (code "107") (name "unconnected-(PORT4-Pad2)") (class "Default")
      (node (ref "PORT4") (pin "2") (pinfunction "2_2") (pintype "bidirectional"))
    )
    (net (code "108") (name "unconnected-(PORT4-Pad8)") (class "Default")
      (node (ref "PORT4") (pin "8") (pinfunction "8_8") (pintype "bidirectional"))
    )
    (net (code "109") (name "unconnected-(SERIAL1-Pad5)") (class "Default")
      (node (ref "SERIAL1") (pin "5") (pinfunction "5_5") (pintype "bidirectional"))
    )
    (net (code "110") (name "unconnected-(SERIAL1-Pad6)") (class "Default")
      (node (ref "SERIAL1") (pin "6") (pinfunction "6_6") (pintype "bidirectional"))
    )
    (net (code "111") (name "unconnected-(SERIAL1-Pad7)") (class "Default")
      (node (ref "SERIAL1") (pin "7") (pinfunction "7_7") (pintype "bidirectional"))
    )
    (net (code "112") (name "unconnected-(SERIAL1-Pad8)") (class "Default")
      (node (ref "SERIAL1") (pin "8") (pinfunction "8_8") (pintype "bidirectional"))
    )
    (net (code "113") (name "unconnected-(SERIAL2-Pad5)") (class "Default")
      (node (ref "SERIAL2") (pin "5") (pinfunction "5_5") (pintype "bidirectional"))
    )
    (net (code "114") (name "unconnected-(SERIAL2-Pad6)") (class "Default")
      (node (ref "SERIAL2") (pin "6") (pinfunction "6_6") (pintype "bidirectional"))
    )
    (net (code "115") (name "unconnected-(SERIAL2-Pad7)") (class "Default")
      (node (ref "SERIAL2") (pin "7") (pinfunction "7_7") (pintype "bidirectional"))
    )
    (net (code "116") (name "unconnected-(SERIAL2-Pad8)") (class "Default")
      (node (ref "SERIAL2") (pin "8") (pinfunction "8_8") (pintype "bidirectional"))
    )
    (net (code "117") (name "unconnected-(SERIAL3-Pad7)") (class "Default")
      (node (ref "SERIAL3") (pin "7") (pinfunction "7_7") (pintype "bidirectional"))
    )
    (net (code "118") (name "unconnected-(SERIAL3-Pad8)") (class "Default")
      (node (ref "SERIAL3") (pin "8") (pinfunction "8_8") (pintype "bidirectional"))
    )
    (net (code "119") (name "unconnected-(SERIAL4-Pad7)") (class "Default")
      (node (ref "SERIAL4") (pin "7") (pinfunction "7_7") (pintype "bidirectional"))
    )
    (net (code "120") (name "unconnected-(SERIAL4-Pad8)") (class "Default")
      (node (ref "SERIAL4") (pin "8") (pinfunction "8_8") (pintype "bidirectional"))
    )
    (net (code "121") (name "unconnected-(SERIAL5-Pad7)") (class "Default")
      (node (ref "SERIAL5") (pin "7") (pinfunction "7_7") (pintype "bidirectional"))
    )
    (net (code "122") (name "unconnected-(SERIAL5-Pad8)") (class "Default")
      (node (ref "SERIAL5") (pin "8") (pinfunction "8_8") (pintype "bidirectional"))
    )
    (net (code "123") (name "unconnected-(U$1-11{slash}MOSI0-Pad11)") (class "Default")
      (node (ref "U$1") (pin "11") (pinfunction "11/MOSI0_11") (pintype "bidirectional"))
    )
    (net (code "124") (name "unconnected-(U$1-12{slash}MISO0-Pad12)") (class "Default")
      (node (ref "U$1") (pin "12") (pinfunction "12/MISO0_12") (pintype "bidirectional"))
    )
    (net (code "125") (name "unconnected-(U$1-13{slash}SCK0{slash}LED-Pad13)") (class "Default")
      (node (ref "U$1") (pin "13") (pinfunction "13/SCK0/LED_13") (pintype "bidirectional"))
    )
    (net (code "126") (name "unconnected-(U$1-29{slash}T{slash}PWM-Pad29)") (class "Default")
      (node (ref "U$1") (pin "29") (pinfunction "29/T/PWM_29") (pintype "bidirectional"))
    )
    (net (code "127") (name "unconnected-(U$1-30{slash}T{slash}PWM-Pad30)") (class "Default")
      (node (ref "U$1") (pin "30") (pinfunction "30/T/PWM_30") (pintype "bidirectional"))
    )
    (net (code "128") (name "unconnected-(U$1-A21{slash}DAC0-PadA21)") (class "Default")
      (node (ref "U$1") (pin "A21") (pinfunction "A21/DAC0_A21") (pintype "bidirectional"))
    )
    (net (code "129") (name "unconnected-(U$1-A22{slash}DAC1-PadA22)") (class "Default")
      (node (ref "U$1") (pin "A22") (pinfunction "A22/DAC1_A22") (pintype "bidirectional"))
    )
    (net (code "130") (name "unconnected-(U$1-Pad24)") (class "Default")
      (node (ref "U$1") (pin "24") (pinfunction "24_24") (pintype "bidirectional"))
    )
    (net (code "131") (name "unconnected-(U$1-Pad25)") (class "Default")
      (node (ref "U$1") (pin "25") (pinfunction "25_25") (pintype "bidirectional"))
    )
    (net (code "132") (name "unconnected-(U$1-Pad26)") (class "Default")
      (node (ref "U$1") (pin "26") (pinfunction "26_26") (pintype "bidirectional"))
    )
    (net (code "133") (name "unconnected-(U$1-Pad28)") (class "Default")
      (node (ref "U$1") (pin "28") (pinfunction "28_28") (pintype "bidirectional"))
    )
  )
)
